# 555.net
KiCad netlist of a schematic drawn in Altium Designer
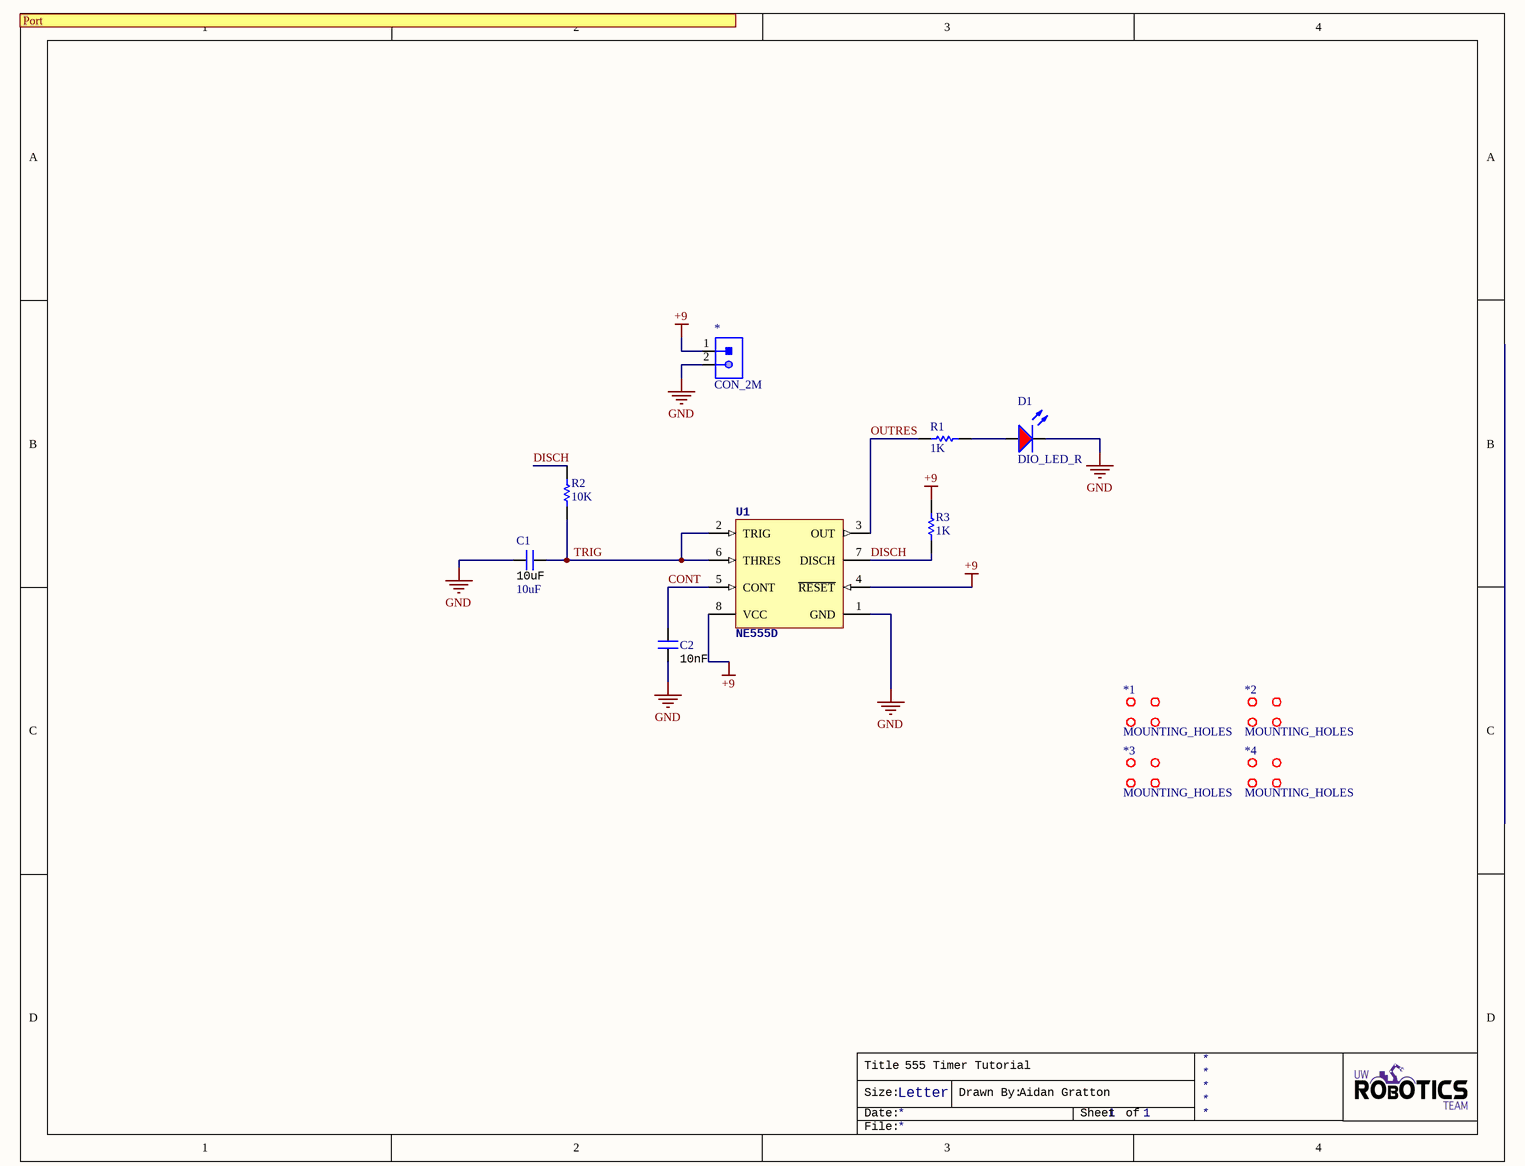
[diagram p0: 555.SchDoc]

(export (version "E")
  (design (tool "Eeschema 10.0.6"))
  (components
    (comp (ref "*")
      (value "CON_2M")
      (footprint "JST-B2B-PHSK")
      (libsource (lib "UWRT_Schematic_Library_2020") (part "CON_2M"))
    )
    (comp (ref "*1")
      (value "MOUNTING_HOLES")
      (footprint "MOUNTING_HOLE")
      (description "6cm x 6cm")
      (libsource (lib "UWRT_Schematic_Library_2020") (part "MOUNTING_HOLES"))
    )
    (comp (ref "*2")
      (value "MOUNTING_HOLES")
      (footprint "MOUNTING_HOLE")
      (description "6cm x 6cm")
      (libsource (lib "UWRT_Schematic_Library_2020") (part "MOUNTING_HOLES"))
    )
    (comp (ref "*3")
      (value "MOUNTING_HOLES")
      (footprint "MOUNTING_HOLE")
      (description "6cm x 6cm")
      (libsource (lib "UWRT_Schematic_Library_2020") (part "MOUNTING_HOLES"))
    )
    (comp (ref "*4")
      (value "MOUNTING_HOLES")
      (footprint "MOUNTING_HOLE")
      (description "6cm x 6cm")
      (libsource (lib "UWRT_Schematic_Library_2020") (part "MOUNTING_HOLES"))
    )
    (comp (ref "C1")
      (value "10uF")
      (footprint "CAPC0603(1608)55_N")
      (description "CAP CER 10UF 10V X5R 0603")
      (fields (field (name "MPN") "CC0603MRX5R6BB106") (field (name "MANUFACTURER") "Yageo"))
      (libsource (lib "UWRT_Schematic_Library_2020") (part "CAP_10uF_0603"))
    )
    (comp (ref "C2")
      (value "10nF")
      (footprint "CAPC0603(1608)55_N")
      (description "CAP CER 10000PF 16V X7R 0603")
      (fields (field (name "MPN") "CC0603KRX7R7BB103") (field (name "MANUFACTURER") "Yageo"))
      (libsource (lib "UWRT_Schematic_Library_2020") (part "CAP_10nF_0603"))
    )
    (comp (ref "D1")
      (value "DIO_LED_R")
      (footprint "LED_0805_LINE")
      (description "LED RED DIFFUSED 0805 SMD")
      (fields (field (name "MPN") "LS R976-NR-1") (field (name "MANUFACTURER") "OSRAM"))
      (libsource (lib "UWRT_Schematic_Library_2020") (part "DIO_LED_R"))
    )
    (comp (ref "R1")
      (value "1K")
      (footprint "RESC0603(1608)_N")
      (description "RES SMD 1K OHM 5% 1/10W 0603")
      (fields (field (name "TOLERANCE") "5%") (field (name "MANUFACTURER") "Yageo"))
      (libsource (lib "UWRT_Schematic_Library_2020") (part "RES_1K_0603"))
    )
    (comp (ref "R2")
      (value "10K")
      (footprint "RESC0603(1608)_N")
      (description "RES SMD 10K OHM 5% 1/10W 0603")
      (fields (field (name "MANUFACTURER") "Yageo") (field (name "MPN") "RC0603JR-0710KL"))
      (libsource (lib "UWRT_Schematic_Library_2020") (part "RES_10K_0603"))
    )
    (comp (ref "R3")
      (value "1K")
      (footprint "RESC0603(1608)_N")
      (description "RES SMD 1K OHM 5% 1/10W 0603")
      (fields (field (name "TOLERANCE") "5%") (field (name "MANUFACTURER") "Yageo"))
      (libsource (lib "UWRT_Schematic_Library_2020") (part "RES_1K_0603"))
    )
    (comp (ref "U1")
      (value "NE555D")
      (footprint "8-SOIC_M")
      (description "Precision Timer, 4.5 to 16 V, 0 to 70 degC, 8-Pin SOIC (D), Green (RoHS & no Sb/Br), Tube")
      (fields (field (name "PARTNUMBER") "NE555") (field (name "MANUFACTURER") "Texas Instruments"))
      (libsource (lib "UWRT_Schematic_Library_2020") (part "NE555D"))
    )
  )
  (nets
    (net (code "1") (name "+9") (class "Default")
      (node (ref "*") (pin "1") (pinfunction "1_1") (pintype "passive"))
      (node (ref "R3") (pin "2") (pinfunction "2_2") (pintype "passive"))
      (node (ref "U1") (pin "4") (pinfunction "~{RESET}_4") (pintype "input"))
      (node (ref "U1") (pin "8") (pinfunction "VCC_8") (pintype "power_in"))
    )
    (net (code "2") (name "/CONT") (class "Default")
      (node (ref "C2") (pin "2") (pinfunction "2_2") (pintype "passive"))
      (node (ref "U1") (pin "5") (pinfunction "CONT_5") (pintype "input"))
    )
    (net (code "3") (name "/DISCH") (class "Default")
      (node (ref "R2") (pin "2") (pinfunction "2_2") (pintype "passive"))
      (node (ref "R3") (pin "1") (pinfunction "1_1") (pintype "passive"))
      (node (ref "U1") (pin "7") (pinfunction "DISCH_7") (pintype "open_collector"))
    )
    (net (code "4") (name "/OUTRES") (class "Default")
      (node (ref "R1") (pin "1") (pinfunction "1_1") (pintype "passive"))
      (node (ref "U1") (pin "3") (pinfunction "OUT_3") (pintype "output"))
    )
    (net (code "6") (name "/TRIG") (class "Default")
      (node (ref "C1") (pin "2") (pinfunction "2_2") (pintype "passive"))
      (node (ref "R2") (pin "1") (pinfunction "1_1") (pintype "passive"))
      (node (ref "U1") (pin "2") (pinfunction "TRIG_2") (pintype "input"))
      (node (ref "U1") (pin "6") (pinfunction "THRES_6") (pintype "input"))
    )
    (net (code "7") (name "GND") (class "Default")
      (node (ref "*") (pin "2") (pinfunction "2_2") (pintype "passive"))
      (node (ref "C1") (pin "1") (pinfunction "1_1") (pintype "passive"))
      (node (ref "C2") (pin "1") (pinfunction "1_1") (pintype "passive"))
      (node (ref "D1") (pin "2") (pinfunction "K_2") (pintype "passive"))
      (node (ref "U1") (pin "1") (pinfunction "GND_1") (pintype "power_in"))
    )
    (net (code "8") (name "Net-(D1-A)") (class "Default")
      (node (ref "D1") (pin "1") (pinfunction "A_1") (pintype "passive"))
      (node (ref "R1") (pin "2") (pinfunction "2_2") (pintype "passive"))
    )
  )
)
